# Adafruit_Flora_GPS.net
KiCad netlist of a schematic drawn in EAGLE
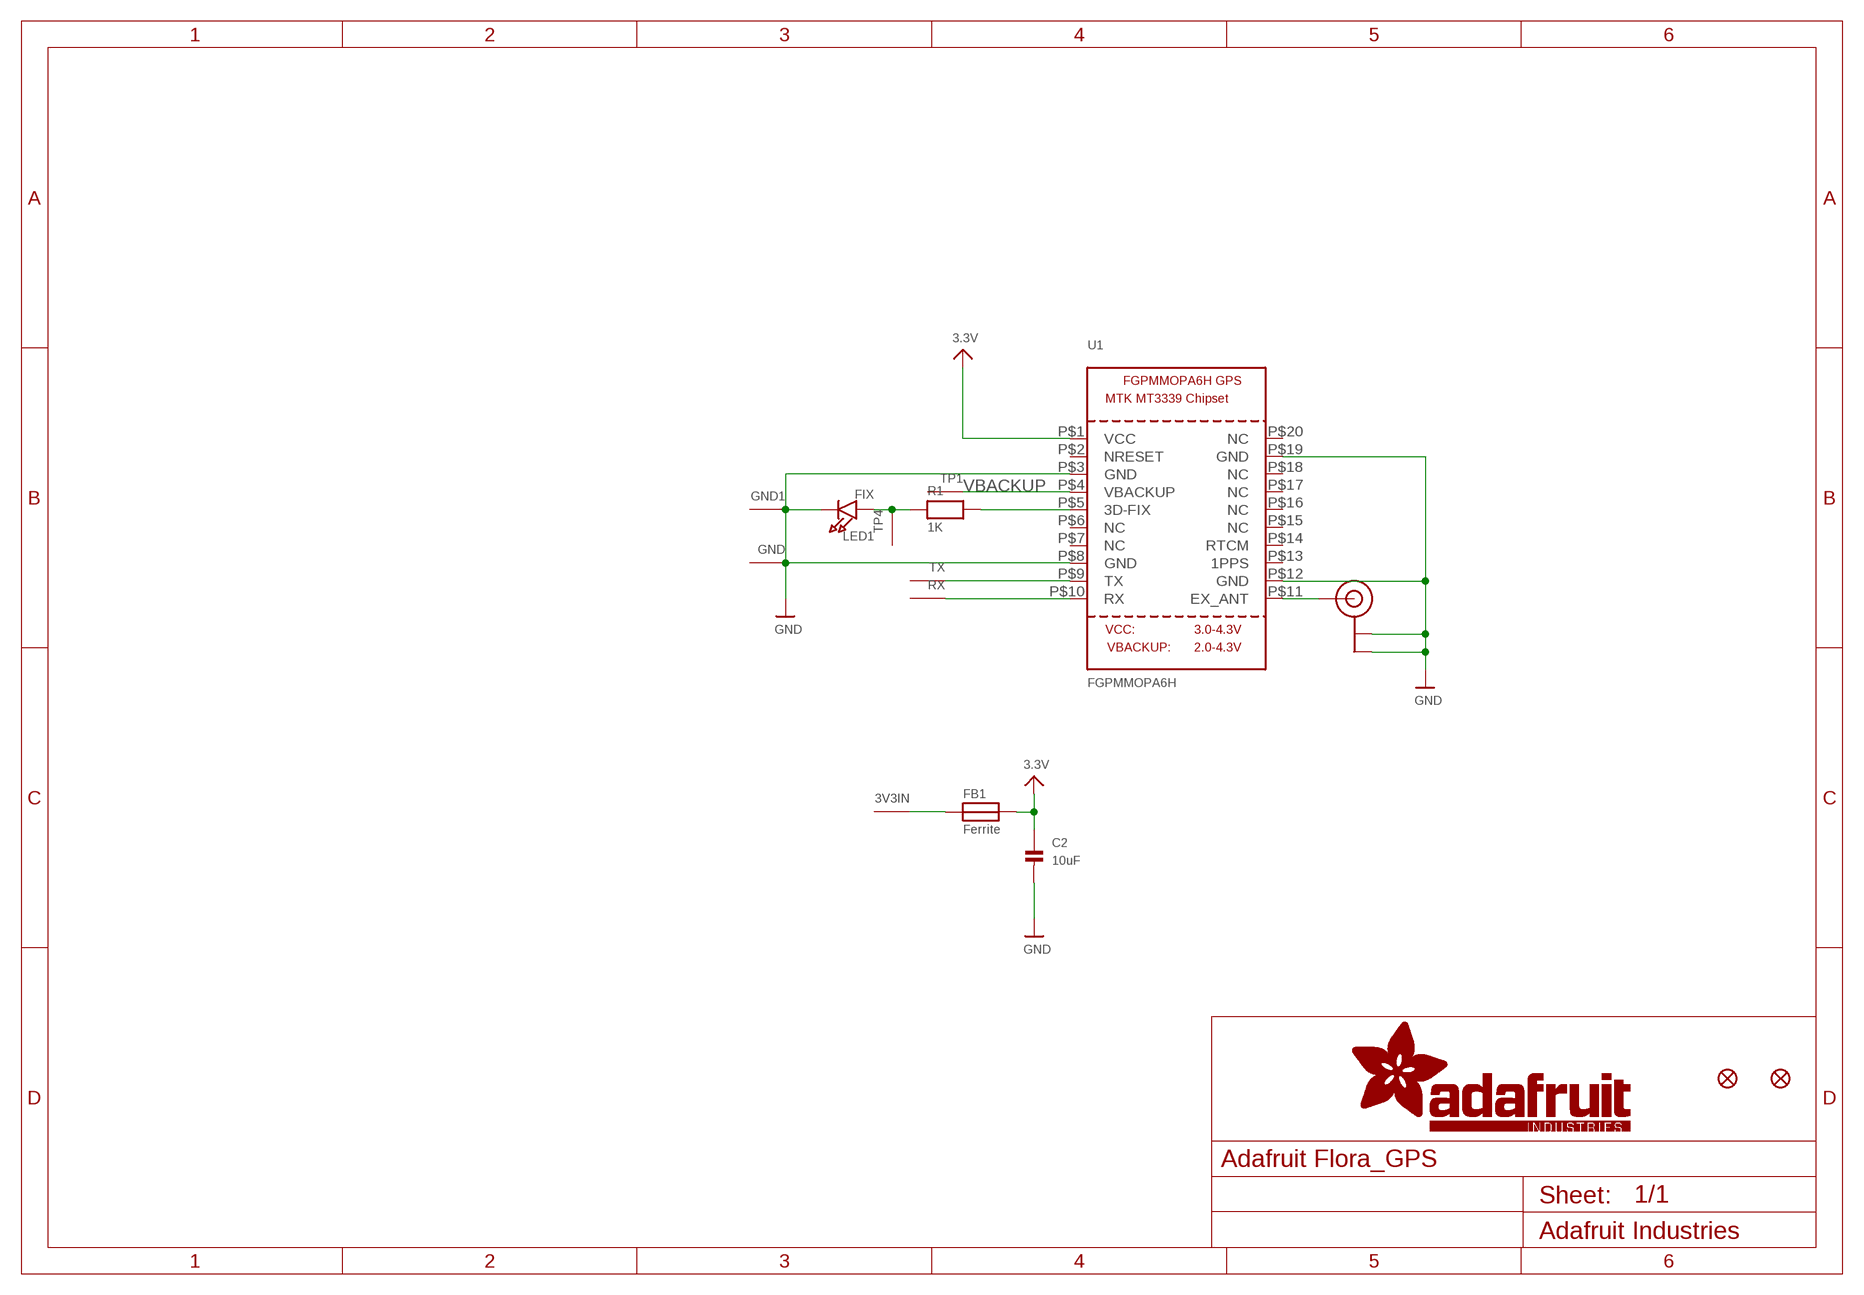
[diagram p0: schematic, sheet 1]

(export (version "E")
  (design (tool "Eeschema 10.0.6"))
  (components
    (comp (ref "3V3IN")
      (value "SEWTAP-2.0IN")
      (footprint "eagle-import:SEWINGTAP_2.0")
      (libsource (lib "eagle-import") (part "SEWTAP-2.0IN"))
    )
    (comp (ref "C2")
      (value "10uF")
      (footprint "eagle-import:0805")
      (libsource (lib "eagle-import") (part "CAP_CERAMIC0805"))
    )
    (comp (ref "FB1")
      (value "Ferrite")
      (footprint "eagle-import:0805")
      (libsource (lib "eagle-import") (part "FERRITE0805"))
    )
    (comp (ref "FID1")
      (value "FIDUCIAL\"\"")
      (footprint "eagle-import:FIDUCIAL_1MM")
      (libsource (lib "eagle-import") (part "FIDUCIAL{dblquote}{dblquote}"))
    )
    (comp (ref "FID2")
      (value "FIDUCIAL\"\"")
      (footprint "eagle-import:FIDUCIAL_1MM")
      (libsource (lib "eagle-import") (part "FIDUCIAL{dblquote}{dblquote}"))
    )
    (comp (ref "GND")
      (value "SEWTAP-2.0IN")
      (footprint "eagle-import:SEWINGTAP_2.0")
      (libsource (lib "eagle-import") (part "SEWTAP-2.0IN"))
    )
    (comp (ref "GND1")
      (value "SEWTAP-2.0IN")
      (footprint "eagle-import:SEWINGTAP_2.0")
      (libsource (lib "eagle-import") (part "SEWTAP-2.0IN"))
    )
    (comp (ref "LED1")
      (value "FIX")
      (footprint "eagle-import:CHIPLED_0805")
      (libsource (lib "eagle-import") (part "LED0805"))
    )
    (comp (ref "R1")
      (value "1K")
      (footprint "eagle-import:0805")
      (libsource (lib "eagle-import") (part "RESISTOR0805"))
    )
    (comp (ref "RX")
      (value "SEWTAP-2.0IN")
      (footprint "eagle-import:SEWINGTAP_2.0")
      (libsource (lib "eagle-import") (part "SEWTAP-2.0IN"))
    )
    (comp (ref "TP1")
      (value "SEWTAP-2.0IN")
      (footprint "eagle-import:SEWINGTAP_2.0")
      (libsource (lib "eagle-import") (part "SEWTAP-2.0IN"))
    )
    (comp (ref "TP4")
      (value "SEWTAP-2.0IN")
      (footprint "eagle-import:SEWINGTAP_2.0")
      (libsource (lib "eagle-import") (part "SEWTAP-2.0IN"))
    )
    (comp (ref "TX")
      (value "SEWTAP-2.0IN")
      (footprint "eagle-import:SEWINGTAP_2.0")
      (libsource (lib "eagle-import") (part "SEWTAP-2.0IN"))
    )
    (comp (ref "U$20")
      (value "U.FL")
      (footprint "eagle-import:U.FL")
      (libsource (lib "eagle-import") (part "U.FL"))
    )
    (comp (ref "U1")
      (value "FGPMMOPA6H")
      (footprint "eagle-import:FGPMMOPA6H")
      (libsource (lib "eagle-import") (part "GPS_FGPMMOPA6H"))
    )
  )
  (nets
    (net (code "1") (name "/VBACKUP") (class "Default")
      (node (ref "TP1") (pin "P$1") (pinfunction "SEW_P$1") (pintype "bidirectional"))
      (node (ref "U1") (pin "P$4") (pinfunction "VBACKUP_P$4") (pintype "bidirectional"))
    )
    (net (code "2") (name "3.3V") (class "Default")
      (node (ref "C2") (pin "1") (pinfunction "P$1_1") (pintype "passive"))
      (node (ref "FB1") (pin "2") (pinfunction "P$2_2") (pintype "bidirectional"))
      (node (ref "U1") (pin "P$1") (pinfunction "VCC_P$1") (pintype "bidirectional"))
    )
    (net (code "3") (name "GND") (class "Default")
      (node (ref "C2") (pin "2") (pinfunction "P$2_2") (pintype "passive"))
      (node (ref "GND") (pin "P$1") (pinfunction "SEW_P$1") (pintype "bidirectional"))
      (node (ref "GND1") (pin "P$1") (pinfunction "SEW_P$1") (pintype "bidirectional"))
      (node (ref "LED1") (pin "C") (pinfunction "C_C") (pintype "passive"))
      (node (ref "U$20") (pin "P$1") (pinfunction "GND_P$1") (pintype "bidirectional"))
      (node (ref "U$20") (pin "P$2") (pinfunction "GND_P$2") (pintype "bidirectional"))
      (node (ref "U1") (pin "P$12") (pinfunction "GND_P$12") (pintype "bidirectional"))
      (node (ref "U1") (pin "P$19") (pinfunction "GND_P$19") (pintype "bidirectional"))
      (node (ref "U1") (pin "P$3") (pinfunction "GND_P$3") (pintype "bidirectional"))
      (node (ref "U1") (pin "P$8") (pinfunction "GND_P$8") (pintype "bidirectional"))
    )
    (net (code "4") (name "Net-(3V3IN-SEW)") (class "Default")
      (node (ref "3V3IN") (pin "P$1") (pinfunction "SEW_P$1") (pintype "bidirectional"))
      (node (ref "FB1") (pin "1") (pinfunction "P$1_1") (pintype "bidirectional"))
    )
    (net (code "5") (name "Net-(RX-SEW)") (class "Default")
      (node (ref "RX") (pin "P$1") (pinfunction "SEW_P$1") (pintype "bidirectional"))
      (node (ref "U1") (pin "P$10") (pinfunction "RX_P$10") (pintype "bidirectional"))
    )
    (net (code "6") (name "Net-(TP4-SEW)") (class "Default")
      (node (ref "LED1") (pin "A") (pinfunction "A_A") (pintype "passive"))
      (node (ref "R1") (pin "1") (pinfunction "1_1") (pintype "passive"))
      (node (ref "TP4") (pin "P$1") (pinfunction "SEW_P$1") (pintype "bidirectional"))
    )
    (net (code "7") (name "Net-(TX-SEW)") (class "Default")
      (node (ref "TX") (pin "P$1") (pinfunction "SEW_P$1") (pintype "bidirectional"))
      (node (ref "U1") (pin "P$9") (pinfunction "TX_P$9") (pintype "bidirectional"))
    )
    (net (code "8") (name "Net-(U$20-SIGNAL)") (class "Default")
      (node (ref "U$20") (pin "P$3") (pinfunction "SIGNAL_P$3") (pintype "bidirectional"))
      (node (ref "U1") (pin "P$11") (pinfunction "EX_ANT_P$11") (pintype "bidirectional"))
    )
    (net (code "9") (name "Net-(U1-3D-FIX)") (class "Default")
      (node (ref "R1") (pin "2") (pinfunction "2_2") (pintype "passive"))
      (node (ref "U1") (pin "P$5") (pinfunction "3D-FIX_P$5") (pintype "bidirectional"))
    )
    (net (code "10") (name "unconnected-(U1-1PPS-PadP$13)") (class "Default")
      (node (ref "U1") (pin "P$13") (pinfunction "1PPS_P$13") (pintype "bidirectional"))
    )
    (net (code "11") (name "unconnected-(U1-NC-PadP$6)") (class "Default")
      (node (ref "U1") (pin "P$6") (pinfunction "NC_P$6") (pintype "bidirectional"))
    )
    (net (code "12") (name "unconnected-(U1-NC-PadP$7)") (class "Default")
      (node (ref "U1") (pin "P$7") (pinfunction "NC_P$7") (pintype "bidirectional"))
    )
    (net (code "13") (name "unconnected-(U1-NC-PadP$15)") (class "Default")
      (node (ref "U1") (pin "P$15") (pinfunction "NC_P$15") (pintype "bidirectional"))
    )
    (net (code "14") (name "unconnected-(U1-NC-PadP$16)") (class "Default")
      (node (ref "U1") (pin "P$16") (pinfunction "NC_P$16") (pintype "bidirectional"))
    )
    (net (code "15") (name "unconnected-(U1-NC-PadP$17)") (class "Default")
      (node (ref "U1") (pin "P$17") (pinfunction "NC_P$17") (pintype "bidirectional"))
    )
    (net (code "16") (name "unconnected-(U1-NC-PadP$18)") (class "Default")
      (node (ref "U1") (pin "P$18") (pinfunction "NC_P$18") (pintype "bidirectional"))
    )
    (net (code "17") (name "unconnected-(U1-NC-PadP$20)") (class "Default")
      (node (ref "U1") (pin "P$20") (pinfunction "NC_P$20") (pintype "bidirectional"))
    )
    (net (code "18") (name "unconnected-(U1-NRESET-PadP$2)") (class "Default")
      (node (ref "U1") (pin "P$2") (pinfunction "NRESET_P$2") (pintype "bidirectional"))
    )
    (net (code "19") (name "unconnected-(U1-RTCM-PadP$14)") (class "Default")
      (node (ref "U1") (pin "P$14") (pinfunction "RTCM_P$14") (pintype "bidirectional"))
    )
  )
)
